# 5_Buck_5V1A.net
KiCad netlist of a schematic drawn in Altium Designer
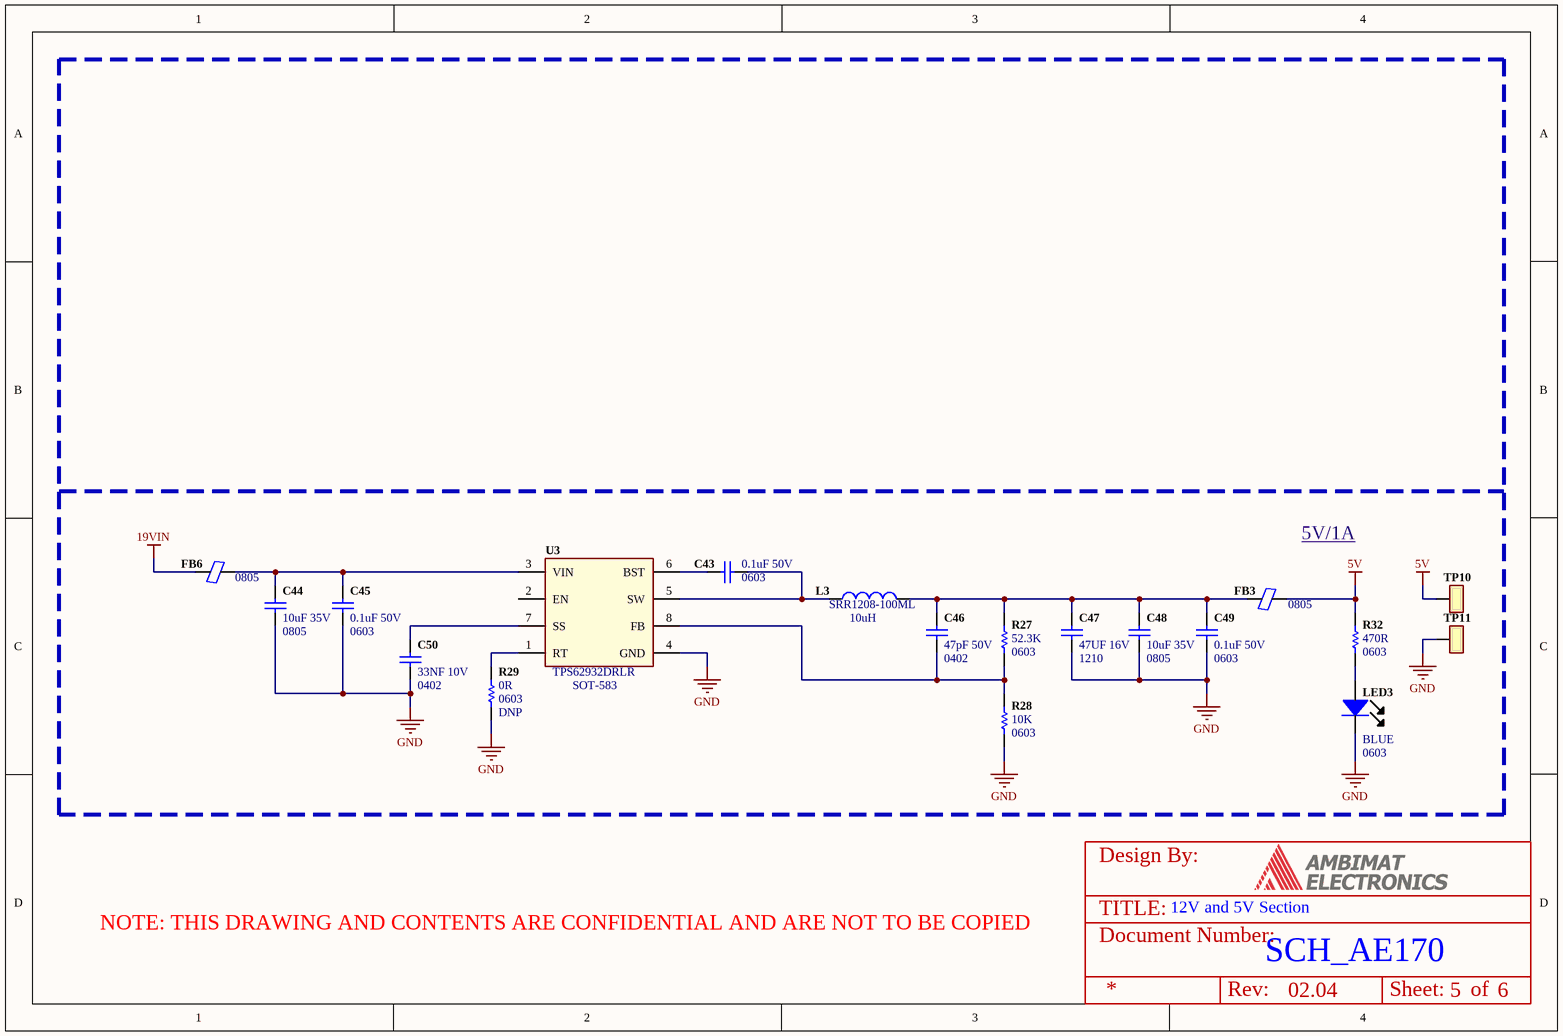
[diagram p0: 5. Buck_5V1A.SchDoc]

(export (version "E")
  (design (tool "Eeschema 10.0.6"))
  (components
    (comp (ref "C43")
      (value "CAP CER 0.1UF 50V X7R 0603")
      (footprint "LimLabDL:0603C")
      (fields
        (field (name "MANU PART NUMBER") "CC0603KRX7R9BB104")
        (field (name "MANUFACTURER") "Yageo")
        (field (name "VENDOR-1 PART NUMBER") "311-1344-1-ND")
        (field (name "PART NAME") "0.1uF 50V")
        (field (name "PCB FOOTPRINT") "0603")
      )
      (libsource (lib "LimLabDL") (part "CS0.1uF-50V0603"))
    )
    (comp (ref "C44")
      (value "CAP CER 10UF 35V X5R 0805")
      (footprint "LimLabDL:0805C")
      (fields
        (field (name "MANU PART NUMBER") "C2012X5R1V106K085AC")
        (field (name "MANUFACTURER") "TDK Corporation")
        (field (name "VENDOR-1 PART NUMBER") "445-14417-1-ND")
        (field (name "PART NAME") "10uF 35V")
        (field (name "PCB FOOTPRINT") "0805")
      )
      (libsource (lib "LimLabDL") (part "CS10uF-35V0805"))
    )
    (comp (ref "C45")
      (value "CAP CER 0.1UF 50V X7R 0603")
      (footprint "LimLabDL:0603C")
      (fields
        (field (name "MANU PART NUMBER") "CC0603KRX7R9BB104")
        (field (name "MANUFACTURER") "Yageo")
        (field (name "VENDOR-1 PART NUMBER") "311-1344-1-ND")
        (field (name "PART NAME") "0.1uF 50V")
        (field (name "PCB FOOTPRINT") "0603")
      )
      (libsource (lib "LimLabDL") (part "CS0.1uF-50V0603"))
    )
    (comp (ref "C46")
      (value "CAP CER 47PF 50V C0G/NP0 0402")
      (footprint "LimLabDL:0402C")
      (fields
        (field (name "MANUFACTURER PART NUMBER") "CL05C470JB5NNNC")
        (field (name "MANUFACTURER") "Samsung Electro-Mechanics")
        (field (name "VENDOR-1 PART NUMBER") "1276-1699-1-ND")
        (field (name "PART NAME") "47pF 50V")
        (field (name "PCB FOOTPRINT") "0402")
      )
      (libsource (lib "LimLabDL") (part "CS47pF-50V0402"))
    )
    (comp (ref "C47")
      (value "CAP CER 47UF 16V X5R 1210")
      (footprint "LimLabDL:1210C")
      (fields
        (field (name "MANUFACTURER PART NUMBER") "GRM32ER61C476KE15L")
        (field (name "MANUFACTURER") "Murata Electronics")
        (field (name "VENDOR-1 PART NUMBER") "490-6539-1-ND")
        (field (name "PART NAME") "47UF 16V")
        (field (name "PCB FOOTPRINT") "1210")
      )
      (libsource (lib "LimLabDL") (part "CS47UF-16V1210"))
    )
    (comp (ref "C48")
      (value "CAP CER 10UF 35V X5R 0805")
      (footprint "LimLabDL:0805C")
      (fields
        (field (name "MANU PART NUMBER") "C2012X5R1V106K085AC")
        (field (name "MANUFACTURER") "TDK Corporation")
        (field (name "VENDOR-1 PART NUMBER") "445-14417-1-ND")
        (field (name "PART NAME") "10uF 35V")
        (field (name "PCB FOOTPRINT") "0805")
      )
      (libsource (lib "LimLabDL") (part "CS10uF-35V0805"))
    )
    (comp (ref "C49")
      (value "CAP CER 0.1UF 50V X7R 0603")
      (footprint "LimLabDL:0603C")
      (fields
        (field (name "MANU PART NUMBER") "CC0603KRX7R9BB104")
        (field (name "MANUFACTURER") "Yageo")
        (field (name "VENDOR-1 PART NUMBER") "311-1344-1-ND")
        (field (name "PART NAME") "0.1uF 50V")
        (field (name "PCB FOOTPRINT") "0603")
      )
      (libsource (lib "LimLabDL") (part "CS0.1uF-50V0603"))
    )
    (comp (ref "C50")
      (value "CAP CER 0.033UF 10V X7R 0402")
      (footprint "LimLabDL:0402C")
      (fields
        (field (name "MANUFACTURER PART NUMBER") "GRM155R71A333KA01D")
        (field (name "MANUFACTURER") "Murata Electronics")
        (field (name "VENDOR-1 PART NUMBER") "490-1315-1-ND")
        (field (name "PART NAME") "33NF 10V")
        (field (name "PCB FOOTPRINT") "0402")
      )
      (libsource (lib "LimLabDL") (part "CS33nF-10V0402"))
    )
    (comp (ref "FB3")
      (value "FERRITE BEAD 120 OHM 0805 1LN")
      (footprint "LimLabDL:0805F")
      (fields
        (field (name "MANUFACTURER") "Pulse Electronics")
        (field (name "MANUFACTURER PART NUMBER") "ABUP00201209121Y00")
        (field (name "VENDOR-1 PART NUMBER") "553-ABUP00201209121Y00CT-ND")
        (field (name "PCB FOOTPRINT") "0805")
      )
      (libsource (lib "LimLabDL") (part "FB120OHM-0805"))
    )
    (comp (ref "FB6")
      (value "FERRITE BEAD 120 OHM 0805 1LN")
      (footprint "LimLabDL:0805F")
      (fields
        (field (name "MANUFACTURER") "Pulse Electronics")
        (field (name "MANUFACTURER PART NUMBER") "ABUP00201209121Y00")
        (field (name "VENDOR-1 PART NUMBER") "553-ABUP00201209121Y00CT-ND")
        (field (name "PCB FOOTPRINT") "0805")
      )
      (libsource (lib "LimLabDL") (part "FB120OHM-0805"))
    )
    (comp (ref "L3")
      (value "FIXED IND 10UH 5A 21 MOHM SMD")
      (footprint "LimLabDL:IND_BOURNS_SRR1208")
      (fields
        (field (name "MANUFACTURER") "Bourns Inc.")
        (field (name "VENDOR-1 PART NUMBER") "SRR1208-100MLCT-ND")
        (field (name "MANU PART NUMBER") "SRR1208-100ML")
        (field (name "PART NAME") "10uH")
      )
      (libsource (lib "LimLabDL") (part "LS10uH 5A-12.7X12.7"))
    )
    (comp (ref "LED3")
      (value "LB Q39G-L2N2-35-1")
      (footprint "LimLabDL:LED0603_BLUE")
      (description "LED BLUE CLEAR 3MM 470NM")
      (fields
        (field (name "MANUFACTURER") "OSRAM Opto Semiconductors Inc")
        (field (name "VENDOR-1 PART NUMBER") "475-2816-1-ND")
        (field (name "PCB FOOTPRINT") "0603")
        (field (name "COLOR") "BLUE")
      )
      (libsource (lib "LimLabDL") (part "LED-BLUE0603"))
    )
    (comp (ref "R27")
      (value "RES 52.3K OHM 1% 1/10W 0603")
      (footprint "LimLabDL:0603")
      (fields
        (field (name "MANU PART NUMBER") "RC0603FR-0752K3L")
        (field (name "MANUFACTURER") "YAGEO")
        (field (name "VENDOR-1 PART NUMBER") "311-52.3KHRCT-ND")
        (field (name "PART NAME") "52.3K")
        (field (name "PCB FOOTPRINT") "0603")
      )
      (libsource (lib "LimLabDL") (part "RS52.3K-0.1W0603"))
    )
    (comp (ref "R28")
      (value "RES SMD 10K OHM 5% 1/10W 0603")
      (footprint "LimLabDL:0603")
      (fields
        (field (name "MANUFACTURER PART NUMBER") "RC0603JR-0710KL")
        (field (name "MANUFACTURER") "Yageo")
        (field (name "VENDOR-1 PART NUMBER") "311-10KGRCT-ND")
        (field (name "PART NAME") "10K")
        (field (name "PCB FOOTPRINT") "0603")
      )
      (libsource (lib "LimLabDL") (part "RS10K-0.1W0603"))
    )
    (comp (ref "R29")
      (value "RES SMD 0 OHM JUMPER 1/10W 0603")
      (footprint "LimLabDL:0603")
      (fields
        (field (name "MOUNTING") "DNP")
        (field (name "MANUFACTURER") "Vishay Dale")
        (field (name "VENDOR-1 PART NUMBER") "541-2971-1-ND")
        (field (name "PART NAME") "0R")
        (field (name "PCB FOOTPRINT") "0603")
        (field (name "MANU PART NUMBER") "CRCW06030000ZSTB")
      )
      (libsource (lib "LimLabDL") (part "RS0R-0.1W0603"))
    )
    (comp (ref "R32")
      (value "RES 470 OHM 1/10W 5% 0603 SMD")
      (footprint "LimLabDL:0603")
      (fields
        (field (name "MANU PART NUMBER") "RC0603JR-07470RL")
        (field (name "MANUFACTURER") "YAGEO")
        (field (name "VENDOR-1 PART NUMBER") "311-470GRCT-ND")
        (field (name "PART NAME") "470R")
        (field (name "PCB FOOTPRINT") "0603")
      )
      (libsource (lib "LimLabDL") (part "RS470R-1/10W0603"))
    )
    (comp (ref "TP10")
      (value "TEST POINT")
      (footprint "LimLabDL:TP-1.5mmSMD")
      (description "SMD TEST POINT")
      (libsource (lib "LimLabDL") (part "TP-1.5mmSMD"))
    )
    (comp (ref "TP11")
      (value "TEST POINT")
      (footprint "LimLabDL:TP-1.5mmSMD")
      (description "SMD TEST POINT")
      (libsource (lib "LimLabDL") (part "TP-1.5mmSMD"))
    )
    (comp (ref "U3")
      (value "IC REG BUCK ADJ 2A SOT583")
      (footprint "LimLabDL:SOT8_DRL_TEX")
      (fields
        (field (name "MANUFACTURER") "Texas Instruments")
        (field (name "VENDOR-1 PART NUMBER") "296-TPS62932DRLRCT-ND")
        (field (name "MANUFACTURER PART NUMBER") "TPS62932DRLR")
        (field (name "PCB FOOTPRINT") "SOT-583")
        (field (name "PART NAME") "TPS62932DRLR")
      )
      (libsource (lib "LimLabDL") (part "IC8P-TPS62932DRLR"))
    )
  )
  (nets
    (net (code "1") (name "5V") (class "Default")
      (node (ref "FB3") (pin "2") (pinfunction "2_2") (pintype "passive"))
      (node (ref "R32") (pin "2") (pinfunction "2_2") (pintype "passive"))
      (node (ref "TP10") (pin "1") (pinfunction "1_1") (pintype "passive"))
    )
    (net (code "2") (name "19VIN") (class "Default")
      (node (ref "FB6") (pin "1") (pinfunction "1_1") (pintype "passive"))
    )
    (net (code "3") (name "GND") (class "Default")
      (node (ref "C44") (pin "2") (pinfunction "2_2") (pintype "passive"))
      (node (ref "C45") (pin "2") (pinfunction "2_2") (pintype "passive"))
      (node (ref "C47") (pin "1") (pinfunction "1_1") (pintype "passive"))
      (node (ref "C48") (pin "2") (pinfunction "2_2") (pintype "passive"))
      (node (ref "C49") (pin "2") (pinfunction "2_2") (pintype "passive"))
      (node (ref "C50") (pin "1") (pinfunction "1_1") (pintype "passive"))
      (node (ref "LED3") (pin "2") (pinfunction "K_2") (pintype "passive"))
      (node (ref "R28") (pin "1") (pinfunction "1_1") (pintype "passive"))
      (node (ref "R29") (pin "1") (pinfunction "1_1") (pintype "passive"))
      (node (ref "TP11") (pin "1") (pinfunction "1_1") (pintype "passive"))
      (node (ref "U3") (pin "4") (pinfunction "GND_4") (pintype "passive"))
    )
    (net (code "4") (name "Net-(C46-Pad1)") (class "Default")
      (node (ref "C46") (pin "1") (pinfunction "1_1") (pintype "passive"))
      (node (ref "C47") (pin "2") (pinfunction "2_2") (pintype "passive"))
      (node (ref "C48") (pin "1") (pinfunction "1_1") (pintype "passive"))
      (node (ref "C49") (pin "1") (pinfunction "1_1") (pintype "passive"))
      (node (ref "FB3") (pin "1") (pinfunction "1_1") (pintype "passive"))
      (node (ref "L3") (pin "2") (pinfunction "2_2") (pintype "passive"))
      (node (ref "R27") (pin "2") (pinfunction "2_2") (pintype "passive"))
    )
    (net (code "5") (name "Net-(LED3-A)") (class "Default")
      (node (ref "LED3") (pin "1") (pinfunction "A_1") (pintype "passive"))
      (node (ref "R32") (pin "1") (pinfunction "1_1") (pintype "passive"))
    )
    (net (code "6") (name "Net-(U3-BST)") (class "Default")
      (node (ref "C43") (pin "1") (pinfunction "1_1") (pintype "passive"))
      (node (ref "U3") (pin "6") (pinfunction "BST_6") (pintype "passive"))
    )
    (net (code "7") (name "Net-(U3-FB)") (class "Default")
      (node (ref "C46") (pin "2") (pinfunction "2_2") (pintype "passive"))
      (node (ref "R27") (pin "1") (pinfunction "1_1") (pintype "passive"))
      (node (ref "R28") (pin "2") (pinfunction "2_2") (pintype "passive"))
      (node (ref "U3") (pin "8") (pinfunction "FB_8") (pintype "passive"))
    )
    (net (code "8") (name "Net-(U3-RT)") (class "Default")
      (node (ref "R29") (pin "2") (pinfunction "2_2") (pintype "passive"))
      (node (ref "U3") (pin "1") (pinfunction "RT_1") (pintype "passive"))
    )
    (net (code "9") (name "Net-(U3-SS)") (class "Default")
      (node (ref "C50") (pin "2") (pinfunction "2_2") (pintype "passive"))
      (node (ref "U3") (pin "7") (pinfunction "SS_7") (pintype "passive"))
    )
    (net (code "10") (name "Net-(U3-SW)") (class "Default")
      (node (ref "C43") (pin "2") (pinfunction "2_2") (pintype "passive"))
      (node (ref "L3") (pin "1") (pinfunction "1_1") (pintype "passive"))
      (node (ref "U3") (pin "5") (pinfunction "SW_5") (pintype "passive"))
    )
    (net (code "11") (name "Net-(U3-VIN)") (class "Default")
      (node (ref "C44") (pin "1") (pinfunction "1_1") (pintype "passive"))
      (node (ref "C45") (pin "1") (pinfunction "1_1") (pintype "passive"))
      (node (ref "FB6") (pin "2") (pinfunction "2_2") (pintype "passive"))
      (node (ref "U3") (pin "3") (pinfunction "VIN_3") (pintype "passive"))
    )
    (net (code "12") (name "unconnected-(U3-EN-Pad2)") (class "Default")
      (node (ref "U3") (pin "2") (pinfunction "EN_2") (pintype "passive"))
    )
  )
)
